# bootloader_burner.net
KiCad netlist of a schematic drawn in EAGLE
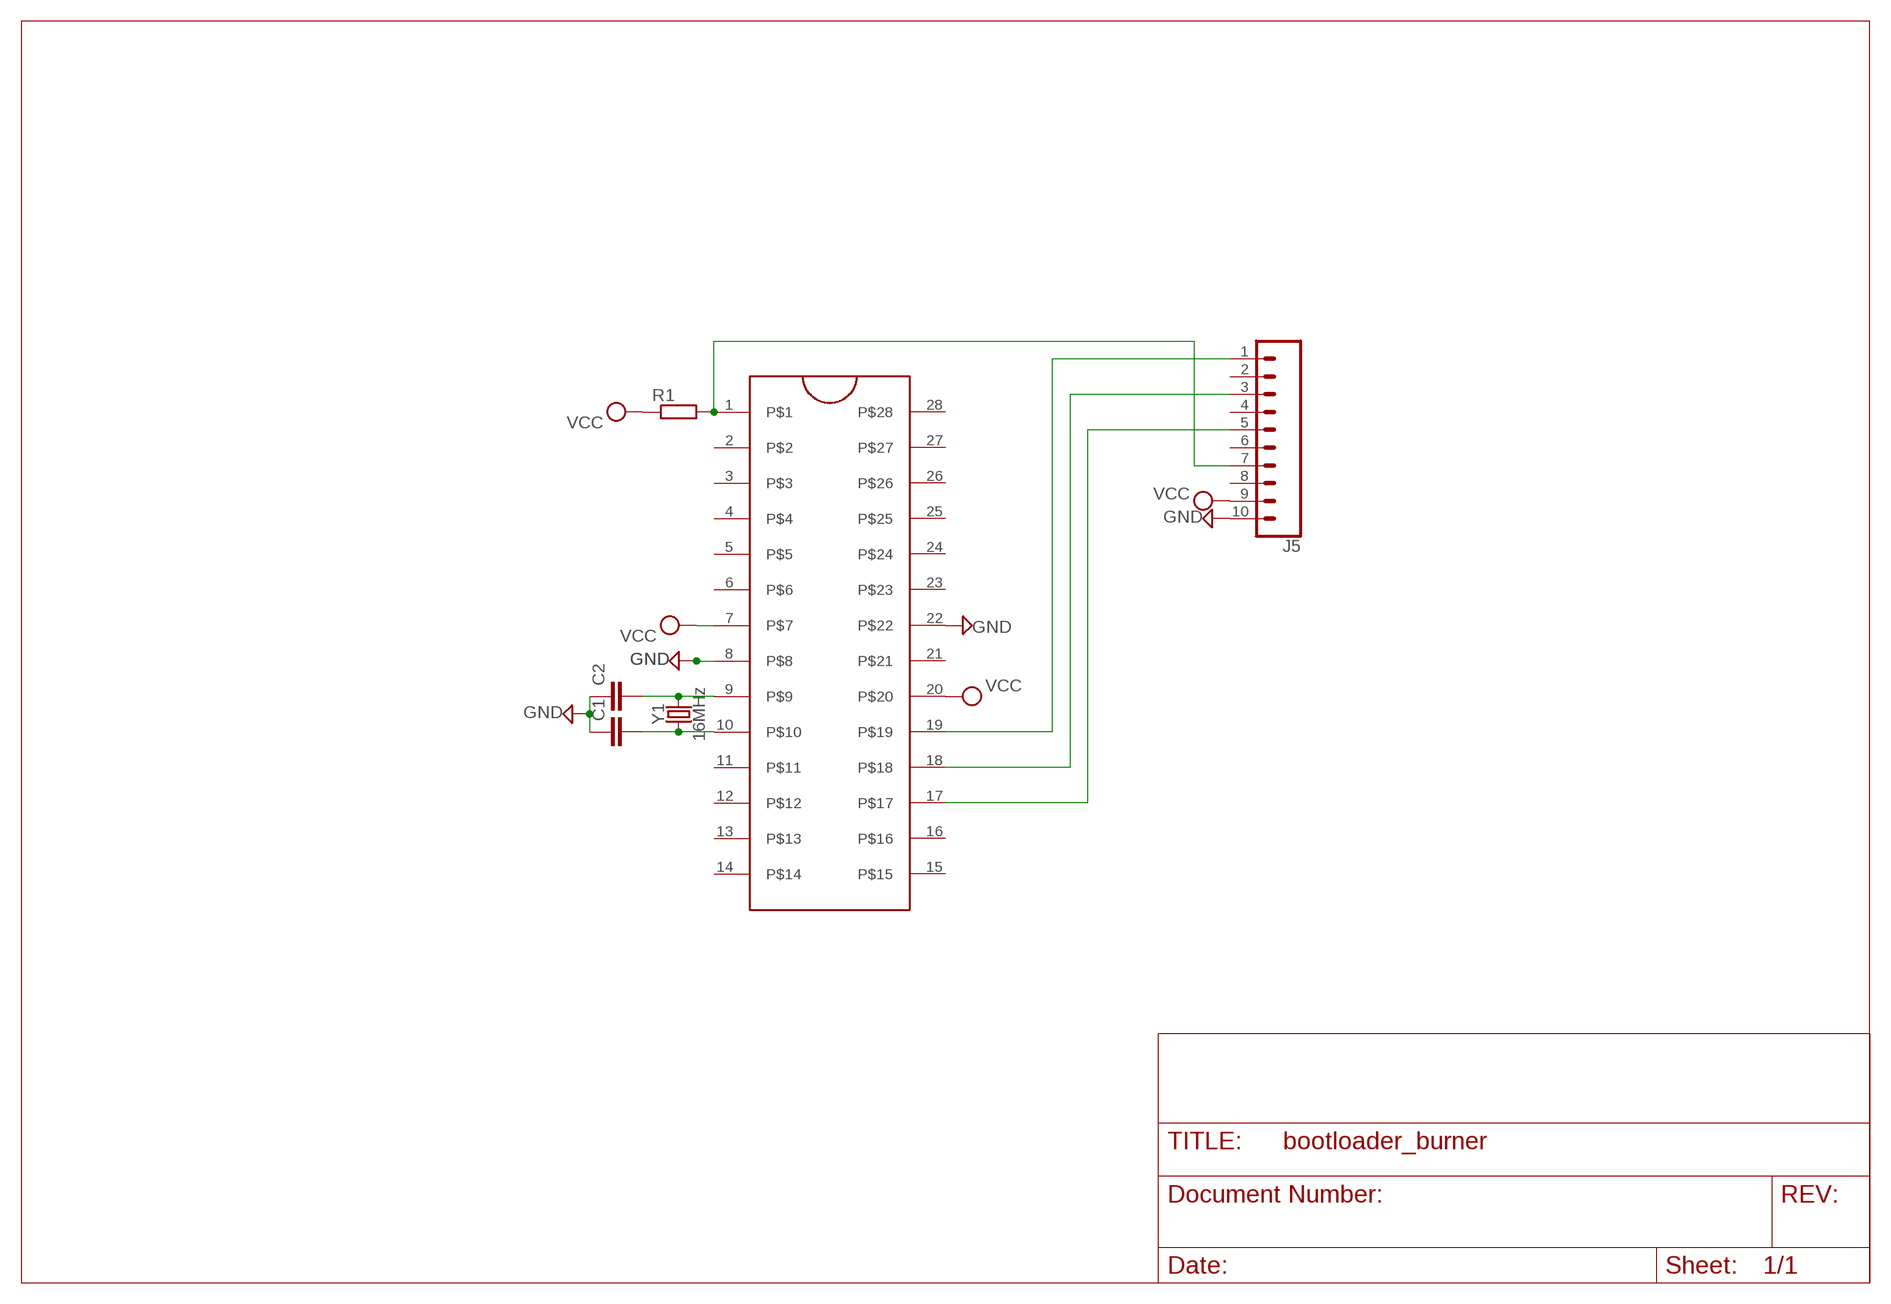
[diagram p0: schematic, sheet 1]

(export (version "E")
  (design (tool "Eeschema 10.0.6"))
  (components
    (comp (ref "C1")
      (value "C-EU025-025X050")
      (footprint "eagle-import:C025-025X050")
      (libsource (lib "eagle-import") (part "C-EU025-025X050"))
    )
    (comp (ref "C2")
      (value "C-EU025-025X050")
      (footprint "eagle-import:C025-025X050")
      (libsource (lib "eagle-import") (part "C-EU025-025X050"))
    )
    (comp (ref "J1")
      (value "ZIFSOCKET-28-3\"")
      (footprint "eagle-import:DIL28-3-ZIF_SOCKET")
      (libsource (lib "eagle-import") (part "ZIFSOCKET-28-3{dblquote}"))
    )
    (comp (ref "J5")
      (value "CONN_10\"")
      (footprint "eagle-import:1X10")
      (libsource (lib "eagle-import") (part "CONN_10{dblquote}"))
    )
    (comp (ref "R1")
      (value "R-EU_0207/10")
      (footprint "eagle-import:0207_10")
      (libsource (lib "eagle-import") (part "R-EU_0207/10"))
    )
    (comp (ref "Y1")
      (value "16MHz")
      (footprint "eagle-import:HC49US")
      (libsource (lib "eagle-import") (part "CRYSTAL-16MHZPTH-HC49US"))
    )
  )
  (nets
    (net (code "1") (name "GND") (class "Default")
      (node (ref "C1") (pin "1") (pinfunction "1_1") (pintype "passive"))
      (node (ref "C2") (pin "1") (pinfunction "1_1") (pintype "passive"))
      (node (ref "J1") (pin "22") (pinfunction "P$22_22") (pintype "bidirectional"))
      (node (ref "J1") (pin "8") (pinfunction "P$8_8") (pintype "bidirectional"))
      (node (ref "J5") (pin "10") (pinfunction "10_10") (pintype "passive"))
    )
    (net (code "2") (name "Net-(J1-P$1)") (class "Default")
      (node (ref "J1") (pin "1") (pinfunction "P$1_1") (pintype "bidirectional"))
      (node (ref "J5") (pin "7") (pinfunction "7_7") (pintype "passive"))
      (node (ref "R1") (pin "2") (pinfunction "2_2") (pintype "passive"))
    )
    (net (code "3") (name "Net-(J1-P$9)") (class "Default")
      (node (ref "C2") (pin "2") (pinfunction "2_2") (pintype "passive"))
      (node (ref "J1") (pin "9") (pinfunction "P$9_9") (pintype "bidirectional"))
      (node (ref "Y1") (pin "2") (pinfunction "2_2") (pintype "passive"))
    )
    (net (code "4") (name "Net-(J1-P$10)") (class "Default")
      (node (ref "C1") (pin "2") (pinfunction "2_2") (pintype "passive"))
      (node (ref "J1") (pin "10") (pinfunction "P$10_10") (pintype "bidirectional"))
      (node (ref "Y1") (pin "1") (pinfunction "1_1") (pintype "passive"))
    )
    (net (code "5") (name "Net-(J1-P$17)") (class "Default")
      (node (ref "J1") (pin "17") (pinfunction "P$17_17") (pintype "bidirectional"))
      (node (ref "J5") (pin "5") (pinfunction "5_5") (pintype "passive"))
    )
    (net (code "6") (name "Net-(J1-P$18)") (class "Default")
      (node (ref "J1") (pin "18") (pinfunction "P$18_18") (pintype "bidirectional"))
      (node (ref "J5") (pin "3") (pinfunction "3_3") (pintype "passive"))
    )
    (net (code "7") (name "Net-(J1-P$19)") (class "Default")
      (node (ref "J1") (pin "19") (pinfunction "P$19_19") (pintype "bidirectional"))
      (node (ref "J5") (pin "1") (pinfunction "1_1") (pintype "passive"))
    )
    (net (code "8") (name "VCC") (class "Default")
      (node (ref "J1") (pin "20") (pinfunction "P$20_20") (pintype "bidirectional"))
      (node (ref "J1") (pin "7") (pinfunction "P$7_7") (pintype "bidirectional"))
      (node (ref "J5") (pin "9") (pinfunction "9_9") (pintype "passive"))
      (node (ref "R1") (pin "1") (pinfunction "1_1") (pintype "passive"))
    )
    (net (code "9") (name "unconnected-(J1-P$2-Pad2)") (class "Default")
      (node (ref "J1") (pin "2") (pinfunction "P$2_2") (pintype "bidirectional"))
    )
    (net (code "10") (name "unconnected-(J1-P$3-Pad3)") (class "Default")
      (node (ref "J1") (pin "3") (pinfunction "P$3_3") (pintype "bidirectional"))
    )
    (net (code "11") (name "unconnected-(J1-P$4-Pad4)") (class "Default")
      (node (ref "J1") (pin "4") (pinfunction "P$4_4") (pintype "bidirectional"))
    )
    (net (code "12") (name "unconnected-(J1-P$5-Pad5)") (class "Default")
      (node (ref "J1") (pin "5") (pinfunction "P$5_5") (pintype "bidirectional"))
    )
    (net (code "13") (name "unconnected-(J1-P$6-Pad6)") (class "Default")
      (node (ref "J1") (pin "6") (pinfunction "P$6_6") (pintype "bidirectional"))
    )
    (net (code "14") (name "unconnected-(J1-P$11-Pad11)") (class "Default")
      (node (ref "J1") (pin "11") (pinfunction "P$11_11") (pintype "bidirectional"))
    )
    (net (code "15") (name "unconnected-(J1-P$12-Pad12)") (class "Default")
      (node (ref "J1") (pin "12") (pinfunction "P$12_12") (pintype "bidirectional"))
    )
    (net (code "16") (name "unconnected-(J1-P$13-Pad13)") (class "Default")
      (node (ref "J1") (pin "13") (pinfunction "P$13_13") (pintype "bidirectional"))
    )
    (net (code "17") (name "unconnected-(J1-P$14-Pad14)") (class "Default")
      (node (ref "J1") (pin "14") (pinfunction "P$14_14") (pintype "bidirectional"))
    )
    (net (code "18") (name "unconnected-(J1-P$15-Pad15)") (class "Default")
      (node (ref "J1") (pin "15") (pinfunction "P$15_15") (pintype "bidirectional"))
    )
    (net (code "19") (name "unconnected-(J1-P$16-Pad16)") (class "Default")
      (node (ref "J1") (pin "16") (pinfunction "P$16_16") (pintype "bidirectional"))
    )
    (net (code "20") (name "unconnected-(J1-P$21-Pad21)") (class "Default")
      (node (ref "J1") (pin "21") (pinfunction "P$21_21") (pintype "bidirectional"))
    )
    (net (code "21") (name "unconnected-(J1-P$23-Pad23)") (class "Default")
      (node (ref "J1") (pin "23") (pinfunction "P$23_23") (pintype "bidirectional"))
    )
    (net (code "22") (name "unconnected-(J1-P$24-Pad24)") (class "Default")
      (node (ref "J1") (pin "24") (pinfunction "P$24_24") (pintype "bidirectional"))
    )
    (net (code "23") (name "unconnected-(J1-P$25-Pad25)") (class "Default")
      (node (ref "J1") (pin "25") (pinfunction "P$25_25") (pintype "bidirectional"))
    )
    (net (code "24") (name "unconnected-(J1-P$26-Pad26)") (class "Default")
      (node (ref "J1") (pin "26") (pinfunction "P$26_26") (pintype "bidirectional"))
    )
    (net (code "25") (name "unconnected-(J1-P$27-Pad27)") (class "Default")
      (node (ref "J1") (pin "27") (pinfunction "P$27_27") (pintype "bidirectional"))
    )
    (net (code "26") (name "unconnected-(J1-P$28-Pad28)") (class "Default")
      (node (ref "J1") (pin "28") (pinfunction "P$28_28") (pintype "bidirectional"))
    )
    (net (code "27") (name "unconnected-(J5-Pad2)") (class "Default")
      (node (ref "J5") (pin "2") (pinfunction "2_2") (pintype "passive"))
    )
    (net (code "28") (name "unconnected-(J5-Pad4)") (class "Default")
      (node (ref "J5") (pin "4") (pinfunction "4_4") (pintype "passive"))
    )
    (net (code "29") (name "unconnected-(J5-Pad6)") (class "Default")
      (node (ref "J5") (pin "6") (pinfunction "6_6") (pintype "passive"))
    )
    (net (code "30") (name "unconnected-(J5-Pad8)") (class "Default")
      (node (ref "J5") (pin "8") (pinfunction "8_8") (pintype "passive"))
    )
  )
)
